# OSV-OL_MOT-DRIV.net
KiCad netlist of a schematic drawn in Altium Designer
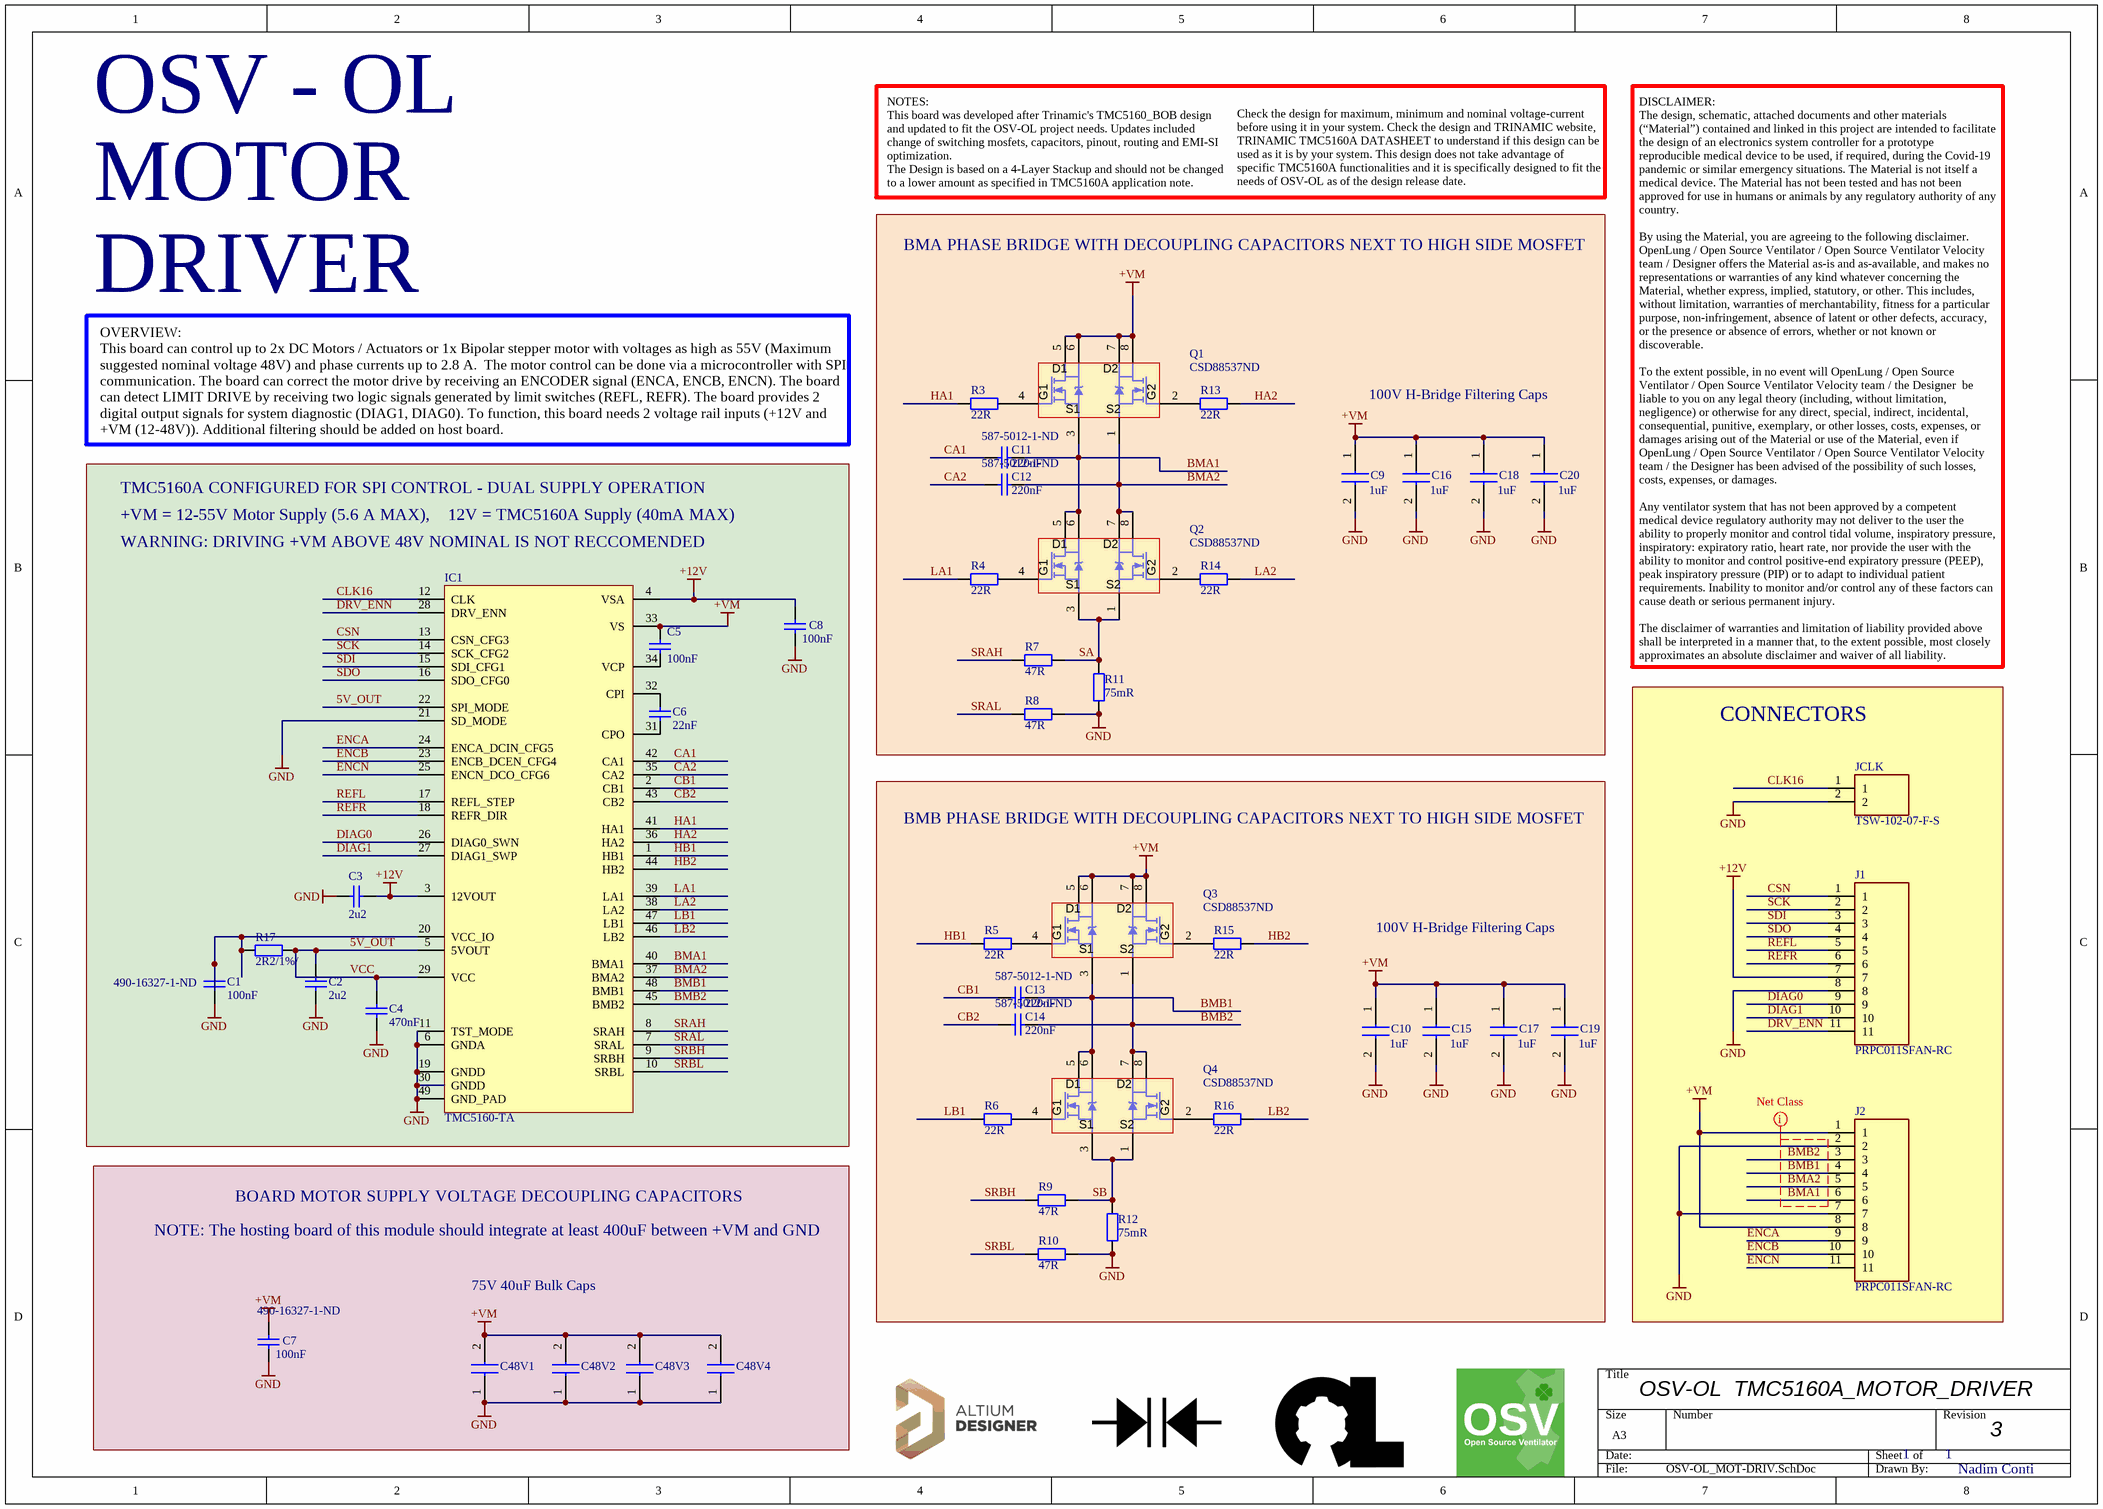
[diagram p0: OSV-OL_MOT-DRIV.SchDoc]

(export (version "E")
  (design (tool "Eeschema 10.0.6"))
  (components
    (comp (ref "C1")
      (value "100nF")
      (footprint "C0603")
      (description "Cap Ceramic 0.1uF 100V X7R 20% Pad SMD 0603 125C T/R")
      (fields
        (field (name "SUPPLIER PART NUMBER 1") "490-16327-1-ND")
        (field (name "MANUFACTURER") "Murata")
        (field (name "MANUFACTURER PART NUMBER") "GRM188R72A104MA35D")
      )
      (libsource (lib "SCH Passives") (part "Capacitor"))
    )
    (comp (ref "C2")
      (value "2u2")
      (footprint "C0603")
      (description "SMD Multilayer Ceramic Capacitor, 0603 [1608 Metric], 2.2 µF, 25 V, ± 10%, X5R, GRM Series")
      (fields (field (name "MF") "MURATA") (field (name "MPN") "GRM188R61E225KA12D"))
      (libsource (lib "TMC5160_RevA") (part "2.2 µF, 25 V, ± 10%, X5R, GRM Series"))
    )
    (comp (ref "C3")
      (value "2u2")
      (footprint "C0603")
      (description "SMD Multilayer Ceramic Capacitor, 0603 [1608 Metric], 2.2 µF, 25 V, ± 10%, X5R, GRM Series")
      (fields (field (name "MF") "MURATA") (field (name "MPN") "GRM188R61E225KA12D"))
      (libsource (lib "TMC5160_RevA") (part "2.2 µF, 25 V, ± 10%, X5R, GRM Series"))
    )
    (comp (ref "C4")
      (value "470nF")
      (footprint "C0603")
      (description "Ceramic capacitor")
      (fields (field (name "MF") "Multicomp") (field (name "MPN") "MC0603X474K160CT"))
      (libsource (lib "SCH Passives") (part "Capacitor"))
    )
    (comp (ref "C5")
      (value "100nF")
      (footprint "C0603")
      (description "Cap Ceramic 0.1uF 100V X7R 20% Pad SMD 0603 125C T/R")
      (fields
        (field (name "MANUFACTURER") "Murata")
        (field (name "MANUFACTURER PART NUMBER") "GRM188R72A104MA35D")
      )
      (libsource (lib "SCH Passives") (part "Capacitor"))
    )
    (comp (ref "C6")
      (value "22nF")
      (footprint "C0603")
      (description "Ceramic capacitor")
      (fields (field (name "MF") "Multicomp") (field (name "MPN") "MC0603B223K500CT"))
      (libsource (lib "SCH Passives") (part "Capacitor"))
    )
    (comp (ref "C7")
      (value "100nF")
      (footprint "C0603")
      (description "Cap Ceramic 0.1uF 100V X7R 20% Pad SMD 0603 125C T/R")
      (fields
        (field (name "SUPPLIER PART NUMBER 1") "490-16327-1-ND")
        (field (name "MANUFACTURER") "Murata")
        (field (name "MANUFACTURER PART NUMBER") "GRM188R72A104MA35D")
      )
      (libsource (lib "SCH Passives") (part "Capacitor"))
    )
    (comp (ref "C8")
      (value "100nF")
      (footprint "C0603")
      (description "Cap Ceramic 0.1uF 100V X7R 20% Pad SMD 0603 125C T/R")
      (fields
        (field (name "MANUFACTURER") "Murata")
        (field (name "MANUFACTURER PART NUMBER") "GRM188R72A104MA35D")
      )
      (libsource (lib "SCH Passives") (part "Capacitor"))
    )
    (comp (ref "C9")
      (value "1uF")
      (footprint "SamacSys:CAPC2012X145N")
      (description "Capacitor")
      (fields
        (field (name "MANUFACTURER_PART_NUMBER") "GRM21BC72A105KE01L")
        (field (name "MOUSER PART NUMBER") "81-GRM21BC72A105KE1L")
      )
      (libsource (lib "*") (part "GRM21BC72A105KE01L"))
    )
    (comp (ref "C10")
      (value "1uF")
      (footprint "SamacSys:CAPC2012X145N")
      (description "Capacitor")
      (fields
        (field (name "MANUFACTURER_PART_NUMBER") "GRM21BC72A105KE01L")
        (field (name "MOUSER PART NUMBER") "81-GRM21BC72A105KE1L")
      )
      (libsource (lib "*") (part "GRM21BC72A105KE01L"))
    )
    (comp (ref "C11")
      (value "220nF")
      (footprint "C0402")
      (description "CAP CER 0.22UF 100V X7S 0603")
      (fields
        (field (name "SUPPLIER PART NUMBER 1") "587-5012-1-ND")
        (field (name "MANUFACTURER") "Taiyo Yuden")
        (field (name "MANUFACTURER PART NUMBER") "HMK107C7224KAHTE")
      )
      (libsource (lib "TMC5160_RevA") (part "0.22 µF, 50 V, ± 10%, X7R"))
    )
    (comp (ref "C12")
      (value "220nF")
      (footprint "C0402")
      (description "CAP CER 0.22UF 100V X7S 0603")
      (fields
        (field (name "SUPPLIER PART NUMBER 1") "587-5012-1-ND")
        (field (name "MANUFACTURER") "Taiyo Yuden")
        (field (name "MANUFACTURER PART NUMBER") "HMK107C7224KAHTE")
      )
      (libsource (lib "TMC5160_RevA") (part "0.22 µF, 50 V, ± 10%, X7R"))
    )
    (comp (ref "C13")
      (value "220nF")
      (footprint "C0402")
      (description "CAP CER 0.22UF 100V X7S 0603")
      (fields
        (field (name "SUPPLIER PART NUMBER 1") "587-5012-1-ND")
        (field (name "MANUFACTURER") "Taiyo Yuden")
        (field (name "MANUFACTURER PART NUMBER") "HMK107C7224KAHTE")
      )
      (libsource (lib "TMC5160_RevA") (part "0.22 µF, 50 V, ± 10%, X7R"))
    )
    (comp (ref "C14")
      (value "220nF")
      (footprint "C0402")
      (description "CAP CER 0.22UF 100V X7S 0603")
      (fields
        (field (name "SUPPLIER PART NUMBER 1") "587-5012-1-ND")
        (field (name "MANUFACTURER") "Taiyo Yuden")
        (field (name "MANUFACTURER PART NUMBER") "HMK107C7224KAHTE")
      )
      (libsource (lib "TMC5160_RevA") (part "0.22 µF, 50 V, ± 10%, X7R"))
    )
    (comp (ref "C15")
      (value "1uF")
      (footprint "SamacSys:CAPC2012X145N")
      (description "Capacitor")
      (fields
        (field (name "MANUFACTURER_PART_NUMBER") "GRM21BC72A105KE01L")
        (field (name "MOUSER PART NUMBER") "81-GRM21BC72A105KE1L")
      )
      (libsource (lib "*") (part "GRM21BC72A105KE01L"))
    )
    (comp (ref "C16")
      (value "1uF")
      (footprint "SamacSys:CAPC2012X145N")
      (description "Capacitor")
      (fields
        (field (name "MANUFACTURER_PART_NUMBER") "GRM21BC72A105KE01L")
        (field (name "MOUSER PART NUMBER") "81-GRM21BC72A105KE1L")
      )
      (libsource (lib "*") (part "GRM21BC72A105KE01L"))
    )
    (comp (ref "C17")
      (value "1uF")
      (footprint "SamacSys:CAPC2012X145N")
      (description "Capacitor")
      (fields
        (field (name "MANUFACTURER_PART_NUMBER") "GRM21BC72A105KE01L")
        (field (name "MOUSER PART NUMBER") "81-GRM21BC72A105KE1L")
      )
      (libsource (lib "*") (part "GRM21BC72A105KE01L"))
    )
    (comp (ref "C18")
      (value "1uF")
      (footprint "SamacSys:CAPC2012X145N")
      (description "Capacitor")
      (fields
        (field (name "MANUFACTURER_PART_NUMBER") "GRM21BC72A105KE01L")
        (field (name "MOUSER PART NUMBER") "81-GRM21BC72A105KE1L")
      )
      (libsource (lib "*") (part "GRM21BC72A105KE01L"))
    )
    (comp (ref "C19")
      (value "1uF")
      (footprint "SamacSys:CAPC2012X145N")
      (description "Capacitor")
      (fields
        (field (name "MANUFACTURER_PART_NUMBER") "GRM21BC72A105KE01L")
        (field (name "MOUSER PART NUMBER") "81-GRM21BC72A105KE1L")
      )
      (libsource (lib "*") (part "GRM21BC72A105KE01L"))
    )
    (comp (ref "C20")
      (value "1uF")
      (footprint "SamacSys:CAPC2012X145N")
      (description "Capacitor")
      (fields
        (field (name "MANUFACTURER_PART_NUMBER") "GRM21BC72A105KE01L")
        (field (name "MOUSER PART NUMBER") "81-GRM21BC72A105KE1L")
      )
      (libsource (lib "*") (part "GRM21BC72A105KE01L"))
    )
    (comp (ref "C48V1")
      (value "C3225X7R1N106K250AC")
      (footprint "SamacSys:CAPC3225X230N")
      (description "Capacitor")
      (fields (field (name "MOUSER PART NUMBER") "810-C3225X7R1N106K25"))
      (libsource (lib "*") (part "C3225X7R1N106K250AC"))
    )
    (comp (ref "C48V2")
      (value "C3225X7R1N106K250AC")
      (footprint "SamacSys:CAPC3225X230N")
      (description "Capacitor")
      (fields (field (name "MOUSER PART NUMBER") "810-C3225X7R1N106K25"))
      (libsource (lib "*") (part "C3225X7R1N106K250AC"))
    )
    (comp (ref "C48V3")
      (value "C3225X7R1N106K250AC")
      (footprint "SamacSys:CAPC3225X230N")
      (description "Capacitor")
      (fields (field (name "MOUSER PART NUMBER") "810-C3225X7R1N106K25"))
      (libsource (lib "*") (part "C3225X7R1N106K250AC"))
    )
    (comp (ref "C48V4")
      (value "C3225X7R1N106K250AC")
      (footprint "SamacSys:CAPC3225X230N")
      (description "Capacitor")
      (fields (field (name "MOUSER PART NUMBER") "810-C3225X7R1N106K25"))
      (libsource (lib "*") (part "C3225X7R1N106K250AC"))
    )
    (comp (ref "IC1")
      (value "TMC5160-TA")
      (footprint "TMC5160_TSQFP50P900X900X120_HS-49L")
      (fields (field (name "MANUFACTURER") "TRINAMIC"))
      (libsource (lib "TMC5160_RevA") (part "TMC5160-TA"))
    )
    (comp (ref "J1")
      (value "PRPC011SFAN-RC")
      (footprint "SamacSys:HDRV11W64P254_1X11_2794X254X1058P")
      (description "Connector")
      (libsource (lib "*") (part "PRPC011SFAN-RC"))
    )
    (comp (ref "J2")
      (value "PRPC011SFAN-RC")
      (footprint "SamacSys:HDRV11W64P254_1X11_2794X254X1058P")
      (description "Connector")
      (libsource (lib "*") (part "PRPC011SFAN-RC"))
    )
    (comp (ref "JCLK")
      (value "TSW-102-07-F-S")
      (footprint "SamacSys:HDRV2W64P254_1X2_508X241X838P")
      (description "Connector")
      (fields (field (name "MOUSER PART NUMBER") "200-TSW10207FS") (field (name "RS PART NUMBER") "1557967"))
      (libsource (lib "*") (part "TSW-102-07-F-S"))
    )
    (comp (ref "Q1")
      (value "CSD88537ND")
      (footprint "SOP127P600X170-8L")
      (description "Mosfet Array 2 N-Channel (Dual) 60V 15A 2.1W Surface Mount 8-SOIC")
      (fields (field (name "MF") "Texas Instruments"))
      (libsource (lib "TMC5160_BOB_V1_2") (part "CSD88537ND MOSFET 2N-CH 60V 15A 8SOIC"))
    )
    (comp (ref "Q2")
      (value "CSD88537ND")
      (footprint "SOP127P600X170-8L")
      (description "Mosfet Array 2 N-Channel (Dual) 60V 15A 2.1W Surface Mount 8-SOIC")
      (fields (field (name "MF") "Texas Instruments"))
      (libsource (lib "TMC5160_BOB_V1_2") (part "CSD88537ND MOSFET 2N-CH 60V 15A 8SOIC"))
    )
    (comp (ref "Q3")
      (value "CSD88537ND")
      (footprint "SOP127P600X170-8L")
      (description "Mosfet Array 2 N-Channel (Dual) 60V 15A 2.1W Surface Mount 8-SOIC")
      (fields (field (name "MF") "Texas Instruments"))
      (libsource (lib "TMC5160_BOB_V1_2") (part "CSD88537ND MOSFET 2N-CH 60V 15A 8SOIC"))
    )
    (comp (ref "Q4")
      (value "CSD88537ND")
      (footprint "SOP127P600X170-8L")
      (description "Mosfet Array 2 N-Channel (Dual) 60V 15A 2.1W Surface Mount 8-SOIC")
      (fields (field (name "MF") "Texas Instruments"))
      (libsource (lib "TMC5160_BOB_V1_2") (part "CSD88537ND MOSFET 2N-CH 60V 15A 8SOIC"))
    )
    (comp (ref "R3")
      (value "22R / 100mW / 1%")
      (footprint "R0603")
      (description "SMD Chip Resistor, Thick Film, 22 ohm, 50 V, 0603 [1608 Metric], 100 mW, ± 1%, MCWR Series")
      (fields
        (field (name "MPN") "MCWR06X22R0FTLV")
        (field (name "MF") "MULTICOMP")
        (field (name "RESISTANCE") "22R")
      )
      (libsource (lib "TMC5160_RevA") (part "22 ohm, 50 V, 0603 [1608 Metric], 100 mW, ± 1%, MCWR Series"))
    )
    (comp (ref "R4")
      (value "22R / 100mW / 1%")
      (footprint "R0603")
      (description "SMD Chip Resistor, Thick Film, 22 ohm, 50 V, 0603 [1608 Metric], 100 mW, ± 1%, MCWR Series")
      (fields
        (field (name "MPN") "MCWR06X22R0FTLV")
        (field (name "MF") "MULTICOMP")
        (field (name "RESISTANCE") "22R")
      )
      (libsource (lib "TMC5160_RevA") (part "22 ohm, 50 V, 0603 [1608 Metric], 100 mW, ± 1%, MCWR Series"))
    )
    (comp (ref "R5")
      (value "22R / 100mW / 1%")
      (footprint "R0603")
      (description "SMD Chip Resistor, Thick Film, 22 ohm, 50 V, 0603 [1608 Metric], 100 mW, ± 1%, MCWR Series")
      (fields
        (field (name "MPN") "MCWR06X22R0FTLV")
        (field (name "MF") "MULTICOMP")
        (field (name "RESISTANCE") "22R")
      )
      (libsource (lib "TMC5160_RevA") (part "22 ohm, 50 V, 0603 [1608 Metric], 100 mW, ± 1%, MCWR Series"))
    )
    (comp (ref "R6")
      (value "22R / 100mW / 1%")
      (footprint "R0603")
      (description "SMD Chip Resistor, Thick Film, 22 ohm, 50 V, 0603 [1608 Metric], 100 mW, ± 1%, MCWR Series")
      (fields
        (field (name "MPN") "MCWR06X22R0FTLV")
        (field (name "MF") "MULTICOMP")
        (field (name "RESISTANCE") "22R")
      )
      (libsource (lib "TMC5160_RevA") (part "22 ohm, 50 V, 0603 [1608 Metric], 100 mW, ± 1%, MCWR Series"))
    )
    (comp (ref "R7")
      (value "47R /  / 1%")
      (footprint "R0603")
      (description "SMD Chip Resistor, Ceramic, 47 ohm, 75 V, 0603 [1608 Metric], 100 mW, ± 1%, MCSR 06 Series")
      (fields
        (field (name "MPN") "MCSR06X47R0FTL")
        (field (name "MF") "MULTICOMP")
        (field (name "RESISTANCE") "47R")
      )
      (libsource (lib "TMC5160_RevA") (part "47 ohm, 75 V, 0603 [1608 Metric], 100 mW, ± 1%, MCSR 06 Series"))
    )
    (comp (ref "R8")
      (value "47R /  / 1%")
      (footprint "R0603")
      (description "SMD Chip Resistor, Ceramic, 47 ohm, 75 V, 0603 [1608 Metric], 100 mW, ± 1%, MCSR 06 Series")
      (fields
        (field (name "MPN") "MCSR06X47R0FTL")
        (field (name "MF") "MULTICOMP")
        (field (name "RESISTANCE") "47R")
      )
      (libsource (lib "TMC5160_RevA") (part "47 ohm, 75 V, 0603 [1608 Metric], 100 mW, ± 1%, MCSR 06 Series"))
    )
    (comp (ref "R9")
      (value "47R /  / 1%")
      (footprint "R0603")
      (description "SMD Chip Resistor, Ceramic, 47 ohm, 75 V, 0603 [1608 Metric], 100 mW, ± 1%, MCSR 06 Series")
      (fields
        (field (name "MPN") "MCSR06X47R0FTL")
        (field (name "MF") "MULTICOMP")
        (field (name "RESISTANCE") "47R")
      )
      (libsource (lib "TMC5160_RevA") (part "47 ohm, 75 V, 0603 [1608 Metric], 100 mW, ± 1%, MCSR 06 Series"))
    )
    (comp (ref "R10")
      (value "47R /  / 1%")
      (footprint "R0603")
      (description "SMD Chip Resistor, Ceramic, 47 ohm, 75 V, 0603 [1608 Metric], 100 mW, ± 1%, MCSR 06 Series")
      (fields
        (field (name "MPN") "MCSR06X47R0FTL")
        (field (name "MF") "MULTICOMP")
        (field (name "RESISTANCE") "47R")
      )
      (libsource (lib "TMC5160_RevA") (part "47 ohm, 75 V, 0603 [1608 Metric], 100 mW, ± 1%, MCSR 06 Series"))
    )
    (comp (ref "R11")
      (value "75mR")
      (footprint "R1206")
      (description "SMD Chip Resistor, Thick Film, Current Sense Resistors - SMD 1W 0.075ohm 1%")
      (fields
        (field (name "MPN") "ERJ-8BWFR075V")
        (field (name "MF") "Panasonic Electronic Components")
        (field (name "RESISTANCE") "75mR")
      )
      (libsource (lib "SMD_Passives") (part "R_SENS, 0.075 ohm, 1206, 1W, ± 1%, ERJ Series"))
    )
    (comp (ref "R12")
      (value "75mR")
      (footprint "R1206")
      (description "SMD Chip Resistor, Thick Film, Current Sense Resistors - SMD 1W 0.075ohm 1%")
      (fields
        (field (name "MPN") "ERJ-8BWFR075V")
        (field (name "MF") "Panasonic Electronic Components")
        (field (name "RESISTANCE") "75mR")
      )
      (libsource (lib "SMD_Passives") (part "R_SENS, 0.075 ohm, 1206, 1W, ± 1%, ERJ Series"))
    )
    (comp (ref "R13")
      (value "22R / 100mW / 1%")
      (footprint "R0603")
      (description "SMD Chip Resistor, Thick Film, 22 ohm, 50 V, 0603 [1608 Metric], 100 mW, ± 1%, MCWR Series")
      (fields
        (field (name "MPN") "MCWR06X22R0FTLV")
        (field (name "MF") "MULTICOMP")
        (field (name "RESISTANCE") "22R")
      )
      (libsource (lib "TMC5160_RevA") (part "22 ohm, 50 V, 0603 [1608 Metric], 100 mW, ± 1%, MCWR Series"))
    )
    (comp (ref "R14")
      (value "22R / 100mW / 1%")
      (footprint "R0603")
      (description "SMD Chip Resistor, Thick Film, 22 ohm, 50 V, 0603 [1608 Metric], 100 mW, ± 1%, MCWR Series")
      (fields
        (field (name "MPN") "MCWR06X22R0FTLV")
        (field (name "MF") "MULTICOMP")
        (field (name "RESISTANCE") "22R")
      )
      (libsource (lib "TMC5160_RevA") (part "22 ohm, 50 V, 0603 [1608 Metric], 100 mW, ± 1%, MCWR Series"))
    )
    (comp (ref "R15")
      (value "22R / 100mW / 1%")
      (footprint "R0603")
      (description "SMD Chip Resistor, Thick Film, 22 ohm, 50 V, 0603 [1608 Metric], 100 mW, ± 1%, MCWR Series")
      (fields
        (field (name "MPN") "MCWR06X22R0FTLV")
        (field (name "MF") "MULTICOMP")
        (field (name "RESISTANCE") "22R")
      )
      (libsource (lib "TMC5160_RevA") (part "22 ohm, 50 V, 0603 [1608 Metric], 100 mW, ± 1%, MCWR Series"))
    )
    (comp (ref "R16")
      (value "22R / 100mW / 1%")
      (footprint "R0603")
      (description "SMD Chip Resistor, Thick Film, 22 ohm, 50 V, 0603 [1608 Metric], 100 mW, ± 1%, MCWR Series")
      (fields
        (field (name "MPN") "MCWR06X22R0FTLV")
        (field (name "MF") "MULTICOMP")
        (field (name "RESISTANCE") "22R")
      )
      (libsource (lib "TMC5160_RevA") (part "22 ohm, 50 V, 0603 [1608 Metric], 100 mW, ± 1%, MCWR Series"))
    )
    (comp (ref "R17")
      (value "2R2/1%/")
      (footprint "R0603")
      (description "Resistor")
      (fields (field (name "MPN") "MC0063W060312R2") (field (name "MF") "Multicomp"))
      (libsource (lib "SCH Passives") (part "Resistor"))
    )
  )
  (nets
    (net (code "1") (name "+12V") (class "Default")
      (node (ref "C3") (pin "2") (pinfunction "2_2") (pintype "passive"))
      (node (ref "C8") (pin "1") (pinfunction "1_1") (pintype "passive"))
      (node (ref "IC1") (pin "3") (pinfunction "12VOUT_3") (pintype "passive"))
      (node (ref "IC1") (pin "4") (pinfunction "VSA_4") (pintype "passive"))
      (node (ref "J1") (pin "7") (pinfunction "7_7") (pintype "passive"))
    )
    (net (code "2") (name "+VM") (class "Default")
      (node (ref "C10") (pin "1") (pinfunction "1_1") (pintype "passive"))
      (node (ref "C15") (pin "1") (pinfunction "1_1") (pintype "passive"))
      (node (ref "C16") (pin "1") (pinfunction "1_1") (pintype "passive"))
      (node (ref "C17") (pin "1") (pinfunction "1_1") (pintype "passive"))
      (node (ref "C18") (pin "1") (pinfunction "1_1") (pintype "passive"))
      (node (ref "C19") (pin "1") (pinfunction "1_1") (pintype "passive"))
      (node (ref "C20") (pin "1") (pinfunction "1_1") (pintype "passive"))
      (node (ref "C48V1") (pin "2") (pinfunction "2_2") (pintype "passive"))
      (node (ref "C48V2") (pin "2") (pinfunction "2_2") (pintype "passive"))
      (node (ref "C48V3") (pin "2") (pinfunction "2_2") (pintype "passive"))
      (node (ref "C48V4") (pin "2") (pinfunction "2_2") (pintype "passive"))
      (node (ref "C5") (pin "1") (pinfunction "1_1") (pintype "passive"))
      (node (ref "C7") (pin "1") (pinfunction "1_1") (pintype "passive"))
      (node (ref "C9") (pin "1") (pinfunction "1_1") (pintype "passive"))
      (node (ref "IC1") (pin "33") (pinfunction "VS_33") (pintype "passive"))
      (node (ref "J2") (pin "1") (pinfunction "1_1") (pintype "passive"))
      (node (ref "J2") (pin "8") (pinfunction "8_8") (pintype "passive"))
      (node (ref "Q1") (pin "5") (pinfunction "D1_5") (pintype "passive"))
      (node (ref "Q1") (pin "6") (pinfunction "D1_6") (pintype "passive"))
      (node (ref "Q1") (pin "7") (pinfunction "D2_7") (pintype "passive"))
      (node (ref "Q1") (pin "8") (pinfunction "D2_8") (pintype "passive"))
      (node (ref "Q3") (pin "5") (pinfunction "D1_5") (pintype "passive"))
      (node (ref "Q3") (pin "6") (pinfunction "D1_6") (pintype "passive"))
      (node (ref "Q3") (pin "7") (pinfunction "D2_7") (pintype "passive"))
      (node (ref "Q3") (pin "8") (pinfunction "D2_8") (pintype "passive"))
    )
    (net (code "3") (name "/5V_OUT") (class "Default")
      (node (ref "C2") (pin "1") (pinfunction "1_1") (pintype "passive"))
      (node (ref "C4") (pin "1") (pinfunction "1_1") (pintype "passive"))
      (node (ref "IC1") (pin "22") (pinfunction "SPI_MODE_22") (pintype "passive"))
      (node (ref "IC1") (pin "29") (pinfunction "VCC_29") (pintype "passive"))
      (node (ref "IC1") (pin "5") (pinfunction "5VOUT_5") (pintype "passive"))
      (node (ref "R17") (pin "2") (pinfunction "2_2") (pintype "passive"))
    )
    (net (code "4") (name "/BMA1") (class "Default")
      (node (ref "C11") (pin "2") (pinfunction "2_2") (pintype "passive"))
      (node (ref "IC1") (pin "40") (pinfunction "BMA1_40") (pintype "passive"))
      (node (ref "J2") (pin "6") (pinfunction "6_6") (pintype "passive"))
      (node (ref "Q1") (pin "3") (pinfunction "S1_3") (pintype "passive"))
      (node (ref "Q2") (pin "5") (pinfunction "D1_5") (pintype "passive"))
      (node (ref "Q2") (pin "6") (pinfunction "D1_6") (pintype "passive"))
    )
    (net (code "5") (name "/BMA2") (class "Default")
      (node (ref "C12") (pin "2") (pinfunction "2_2") (pintype "passive"))
      (node (ref "IC1") (pin "37") (pinfunction "BMA2_37") (pintype "passive"))
      (node (ref "J2") (pin "5") (pinfunction "5_5") (pintype "passive"))
      (node (ref "Q1") (pin "1") (pinfunction "S2_1") (pintype "passive"))
      (node (ref "Q2") (pin "7") (pinfunction "D2_7") (pintype "passive"))
      (node (ref "Q2") (pin "8") (pinfunction "D2_8") (pintype "passive"))
    )
    (net (code "6") (name "/BMB1") (class "Default")
      (node (ref "C13") (pin "2") (pinfunction "2_2") (pintype "passive"))
      (node (ref "IC1") (pin "48") (pinfunction "BMB1_48") (pintype "passive"))
      (node (ref "J2") (pin "4") (pinfunction "4_4") (pintype "passive"))
      (node (ref "Q3") (pin "3") (pinfunction "S1_3") (pintype "passive"))
      (node (ref "Q4") (pin "5") (pinfunction "D1_5") (pintype "passive"))
      (node (ref "Q4") (pin "6") (pinfunction "D1_6") (pintype "passive"))
    )
    (net (code "7") (name "/BMB2") (class "Default")
      (node (ref "C14") (pin "2") (pinfunction "2_2") (pintype "passive"))
      (node (ref "IC1") (pin "45") (pinfunction "BMB2_45") (pintype "passive"))
      (node (ref "J2") (pin "3") (pinfunction "3_3") (pintype "passive"))
      (node (ref "Q3") (pin "1") (pinfunction "S2_1") (pintype "passive"))
      (node (ref "Q4") (pin "7") (pinfunction "D2_7") (pintype "passive"))
      (node (ref "Q4") (pin "8") (pinfunction "D2_8") (pintype "passive"))
    )
    (net (code "8") (name "/CA1") (class "Default")
      (node (ref "C11") (pin "1") (pinfunction "1_1") (pintype "passive"))
      (node (ref "IC1") (pin "42") (pinfunction "CA1_42") (pintype "passive"))
    )
    (net (code "9") (name "/CA2") (class "Default")
      (node (ref "C12") (pin "1") (pinfunction "1_1") (pintype "passive"))
      (node (ref "IC1") (pin "35") (pinfunction "CA2_35") (pintype "passive"))
    )
    (net (code "10") (name "/CB1") (class "Default")
      (node (ref "C13") (pin "1") (pinfunction "1_1") (pintype "passive"))
      (node (ref "IC1") (pin "2") (pinfunction "CB1_2") (pintype "passive"))
    )
    (net (code "11") (name "/CB2") (class "Default")
      (node (ref "C14") (pin "1") (pinfunction "1_1") (pintype "passive"))
      (node (ref "IC1") (pin "43") (pinfunction "CB2_43") (pintype "passive"))
    )
    (net (code "12") (name "/CLK16") (class "Default")
      (node (ref "IC1") (pin "12") (pinfunction "CLK_12") (pintype "passive"))
      (node (ref "JCLK") (pin "1") (pinfunction "1_1") (pintype "passive"))
    )
    (net (code "13") (name "/CSN") (class "Default")
      (node (ref "IC1") (pin "13") (pinfunction "CSN_CFG3_13") (pintype "passive"))
      (node (ref "J1") (pin "1") (pinfunction "1_1") (pintype "passive"))
    )
    (net (code "14") (name "/DIAG0") (class "Default")
      (node (ref "IC1") (pin "26") (pinfunction "DIAG0_SWN_26") (pintype "passive"))
      (node (ref "J1") (pin "9") (pinfunction "9_9") (pintype "passive"))
    )
    (net (code "15") (name "/DIAG1") (class "Default")
      (node (ref "IC1") (pin "27") (pinfunction "DIAG1_SWP_27") (pintype "passive"))
      (node (ref "J1") (pin "10") (pinfunction "10_10") (pintype "passive"))
    )
    (net (code "16") (name "/DRV_ENN") (class "Default")
      (node (ref "IC1") (pin "28") (pinfunction "DRV_ENN_28") (pintype "passive"))
      (node (ref "J1") (pin "11") (pinfunction "11_11") (pintype "passive"))
    )
    (net (code "17") (name "/ENCA") (class "Default")
      (node (ref "IC1") (pin "24") (pinfunction "ENCA_DCIN_CFG5_24") (pintype "passive"))
      (node (ref "J2") (pin "9") (pinfunction "9_9") (pintype "passive"))
    )
    (net (code "18") (name "/ENCB") (class "Default")
      (node (ref "IC1") (pin "23") (pinfunction "ENCB_DCEN_CFG4_23") (pintype "passive"))
      (node (ref "J2") (pin "10") (pinfunction "10_10") (pintype "passive"))
    )
    (net (code "19") (name "/ENCN") (class "Default")
      (node (ref "IC1") (pin "25") (pinfunction "ENCN_DCO_CFG6_25") (pintype "passive"))
      (node (ref "J2") (pin "11") (pinfunction "11_11") (pintype "passive"))
    )
    (net (code "20") (name "/HA1") (class "Default")
      (node (ref "IC1") (pin "41") (pinfunction "HA1_41") (pintype "passive"))
      (node (ref "R3") (pin "2") (pinfunction "2_2") (pintype "passive"))
    )
    (net (code "21") (name "/HA2") (class "Default")
      (node (ref "IC1") (pin "36") (pinfunction "HA2_36") (pintype "passive"))
      (node (ref "R13") (pin "1") (pinfunction "1_1") (pintype "passive"))
    )
    (net (code "22") (name "/HB1") (class "Default")
      (node (ref "IC1") (pin "1") (pinfunction "HB1_1") (pintype "passive"))
      (node (ref "R5") (pin "2") (pinfunction "2_2") (pintype "passive"))
    )
    (net (code "23") (name "/HB2") (class "Default")
      (node (ref "IC1") (pin "44") (pinfunction "HB2_44") (pintype "passive"))
      (node (ref "R15") (pin "1") (pinfunction "1_1") (pintype "passive"))
    )
    (net (code "24") (name "/LA1") (class "Default")
      (node (ref "IC1") (pin "39") (pinfunction "LA1_39") (pintype "passive"))
      (node (ref "R4") (pin "2") (pinfunction "2_2") (pintype "passive"))
    )
    (net (code "25") (name "/LA2") (class "Default")
      (node (ref "IC1") (pin "38") (pinfunction "LA2_38") (pintype "passive"))
      (node (ref "R14") (pin "1") (pinfunction "1_1") (pintype "passive"))
    )
    (net (code "26") (name "/LB1") (class "Default")
      (node (ref "IC1") (pin "47") (pinfunction "LB1_47") (pintype "passive"))
      (node (ref "R6") (pin "2") (pinfunction "2_2") (pintype "passive"))
    )
    (net (code "27") (name "/LB2") (class "Default")
      (node (ref "IC1") (pin "46") (pinfunction "LB2_46") (pintype "passive"))
      (node (ref "R16") (pin "1") (pinfunction "1_1") (pintype "passive"))
    )
    (net (code "28") (name "/REFL") (class "Default")
      (node (ref "IC1") (pin "17") (pinfunction "REFL_STEP_17") (pintype "passive"))
      (node (ref "J1") (pin "5") (pinfunction "5_5") (pintype "passive"))
    )
    (net (code "29") (name "/REFR") (class "Default")
      (node (ref "IC1") (pin "18") (pinfunction "REFR_DIR_18") (pintype "passive"))
      (node (ref "J1") (pin "6") (pinfunction "6_6") (pintype "passive"))
    )
    (net (code "30") (name "/SA") (class "Default")
      (node (ref "Q2") (pin "1") (pinfunction "S2_1") (pintype "passive"))
      (node (ref "Q2") (pin "3") (pinfunction "S1_3") (pintype "passive"))
      (node (ref "R11") (pin "1") (pinfunction "1_1") (pintype "passive"))
      (node (ref "R7") (pin "1") (pinfunction "1_1") (pintype "passive"))
    )
    (net (code "31") (name "/SB") (class "Default")
      (node (ref "Q4") (pin "1") (pinfunction "S2_1") (pintype "passive"))
      (node (ref "Q4") (pin "3") (pinfunction "S1_3") (pintype "passive"))
      (node (ref "R12") (pin "1") (pinfunction "1_1") (pintype "passive"))
      (node (ref "R9") (pin "1") (pinfunction "1_1") (pintype "passive"))
    )
    (net (code "32") (name "/SCK") (class "Default")
      (node (ref "IC1") (pin "14") (pinfunction "SCK_CFG2_14") (pintype "passive"))
      (node (ref "J1") (pin "2") (pinfunction "2_2") (pintype "passive"))
    )
    (net (code "33") (name "/SDI") (class "Default")
      (node (ref "IC1") (pin "15") (pinfunction "SDI_CFG1_15") (pintype "passive"))
      (node (ref "J1") (pin "3") (pinfunction "3_3") (pintype "passive"))
    )
    (net (code "34") (name "/SDO") (class "Default")
      (node (ref "IC1") (pin "16") (pinfunction "SDO_CFG0_16") (pintype "passive"))
      (node (ref "J1") (pin "4") (pinfunction "4_4") (pintype "passive"))
    )
    (net (code "35") (name "/SRAH") (class "Default")
      (node (ref "IC1") (pin "8") (pinfunction "SRAH_8") (pintype "passive"))
      (node (ref "R7") (pin "2") (pinfunction "2_2") (pintype "passive"))
    )
    (net (code "36") (name "/SRAL") (class "Default")
      (node (ref "IC1") (pin "7") (pinfunction "SRAL_7") (pintype "passive"))
      (node (ref "R8") (pin "2") (pinfunction "2_2") (pintype "passive"))
    )
    (net (code "37") (name "/SRBH") (class "Default")
      (node (ref "IC1") (pin "9") (pinfunction "SRBH_9") (pintype "passive"))
      (node (ref "R9") (pin "2") (pinfunction "2_2") (pintype "passive"))
    )
    (net (code "38") (name "/SRBL") (class "Default")
      (node (ref "IC1") (pin "10") (pinfunction "SRBL_10") (pintype "passive"))
      (node (ref "R10") (pin "2") (pinfunction "2_2") (pintype "passive"))
    )
    (net (code "39") (name "GND") (class "Default")
      (node (ref "C1") (pin "2") (pinfunction "2_2") (pintype "passive"))
      (node (ref "C10") (pin "2") (pinfunction "2_2") (pintype "passive"))
      (node (ref "C15") (pin "2") (pinfunction "2_2") (pintype "passive"))
      (node (ref "C16") (pin "2") (pinfunction "2_2") (pintype "passive"))
      (node (ref "C17") (pin "2") (pinfunction "2_2") (pintype "passive"))
      (node (ref "C18") (pin "2") (pinfunction "2_2") (pintype "passive"))
      (node (ref "C19") (pin "2") (pinfunction "2_2") (pintype "passive"))
      (node (ref "C2") (pin "2") (pinfunction "2_2") (pintype "passive"))
      (node (ref "C20") (pin "2") (pinfunction "2_2") (pintype "passive"))
      (node (ref "C3") (pin "1") (pinfunction "1_1") (pintype "passive"))
      (node (ref "C4") (pin "2") (pinfunction "2_2") (pintype "passive"))
      (node (ref "C48V1") (pin "1") (pinfunction "1_1") (pintype "passive"))
      (node (ref "C48V2") (pin "1") (pinfunction "1_1") (pintype "passive"))
      (node (ref "C48V3") (pin "1") (pinfunction "1_1") (pintype "passive"))
      (node (ref "C48V4") (pin "1") (pinfunction "1_1") (pintype "passive"))
      (node (ref "C7") (pin "2") (pinfunction "2_2") (pintype "passive"))
      (node (ref "C8") (pin "2") (pinfunction "2_2") (pintype "passive"))
      (node (ref "C9") (pin "2") (pinfunction "2_2") (pintype "passive"))
      (node (ref "IC1") (pin "11") (pinfunction "TST_MODE_11") (pintype "passive"))
      (node (ref "IC1") (pin "19") (pinfunction "GNDD_19") (pintype "passive"))
      (node (ref "IC1") (pin "21") (pinfunction "SD_MODE_21") (pintype "passive"))
      (node (ref "IC1") (pin "30") (pinfunction "GNDD_30") (pintype "passive"))
      (node (ref "IC1") (pin "49") (pinfunction "GND_PAD_49") (pintype "passive"))
      (node (ref "IC1") (pin "6") (pinfunction "GNDA_6") (pintype "passive"))
      (node (ref "J1") (pin "8") (pinfunction "8_8") (pintype "passive"))
      (node (ref "J2") (pin "2") (pinfunction "2_2") (pintype "passive"))
      (node (ref "J2") (pin "7") (pinfunction "7_7") (pintype "passive"))
      (node (ref "JCLK") (pin "2") (pinfunction "2_2") (pintype "passive"))
      (node (ref "R10") (pin "1") (pinfunction "1_1") (pintype "passive"))
      (node (ref "R11") (pin "2") (pinfunction "2_2") (pintype "passive"))
      (node (ref "R12") (pin "2") (pinfunction "2_2") (pintype "passive"))
      (node (ref "R8") (pin "1") (pinfunction "1_1") (pintype "passive"))
    )
    (net (code "40") (name "Net-(IC1-CPI)") (class "Default")
      (node (ref "C6") (pin "2") (pinfunction "2_2") (pintype "passive"))
      (node (ref "IC1") (pin "32") (pinfunction "CPI_32") (pintype "passive"))
    )
    (net (code "41") (name "Net-(IC1-CPO)") (class "Default")
      (node (ref "C6") (pin "1") (pinfunction "1_1") (pintype "passive"))
      (node (ref "IC1") (pin "31") (pinfunction "CPO_31") (pintype "passive"))
    )
    (net (code "42") (name "Net-(IC1-VCC_IO)") (class "Default")
      (node (ref "C1") (pin "1") (pinfunction "1_1") (pintype "passive"))
      (node (ref "IC1") (pin "20") (pinfunction "VCC_IO_20") (pintype "passive"))
      (node (ref "R17") (pin "1") (pinfunction "1_1") (pintype "passive"))
    )
    (net (code "43") (name "Net-(IC1-VCP)") (class "Default")
      (node (ref "C5") (pin "2") (pinfunction "2_2") (pintype "passive"))
      (node (ref "IC1") (pin "34") (pinfunction "VCP_34") (pintype "passive"))
    )
    (net (code "44") (name "Net-(Q1-G1)") (class "Default")
      (node (ref "Q1") (pin "4") (pinfunction "G1_4") (pintype "passive"))
      (node (ref "R3") (pin "1") (pinfunction "1_1") (pintype "passive"))
    )
    (net (code "45") (name "Net-(Q1-G2)") (class "Default")
      (node (ref "Q1") (pin "2") (pinfunction "G2_2") (pintype "passive"))
      (node (ref "R13") (pin "2") (pinfunction "2_2") (pintype "passive"))
    )
    (net (code "46") (name "Net-(Q2-G1)") (class "Default")
      (node (ref "Q2") (pin "4") (pinfunction "G1_4") (pintype "passive"))
      (node (ref "R4") (pin "1") (pinfunction "1_1") (pintype "passive"))
    )
    (net (code "47") (name "Net-(Q2-G2)") (class "Default")
      (node (ref "Q2") (pin "2") (pinfunction "G2_2") (pintype "passive"))
      (node (ref "R14") (pin "2") (pinfunction "2_2") (pintype "passive"))
    )
    (net (code "48") (name "Net-(Q3-G1)") (class "Default")
      (node (ref "Q3") (pin "4") (pinfunction "G1_4") (pintype "passive"))
      (node (ref "R5") (pin "1") (pinfunction "1_1") (pintype "passive"))
    )
    (net (code "49") (name "Net-(Q3-G2)") (class "Default")
      (node (ref "Q3") (pin "2") (pinfunction "G2_2") (pintype "passive"))
      (node (ref "R15") (pin "2") (pinfunction "2_2") (pintype "passive"))
    )
    (net (code "50") (name "Net-(Q4-G1)") (class "Default")
      (node (ref "Q4") (pin "4") (pinfunction "G1_4") (pintype "passive"))
      (node (ref "R6") (pin "1") (pinfunction "1_1") (pintype "passive"))
    )
    (net (code "51") (name "Net-(Q4-G2)") (class "Default")
      (node (ref "Q4") (pin "2") (pinfunction "G2_2") (pintype "passive"))
      (node (ref "R16") (pin "2") (pinfunction "2_2") (pintype "passive"))
    )
  )
)
